# Basisboard_Weiche.net
KiCad netlist of a schematic drawn in EAGLE
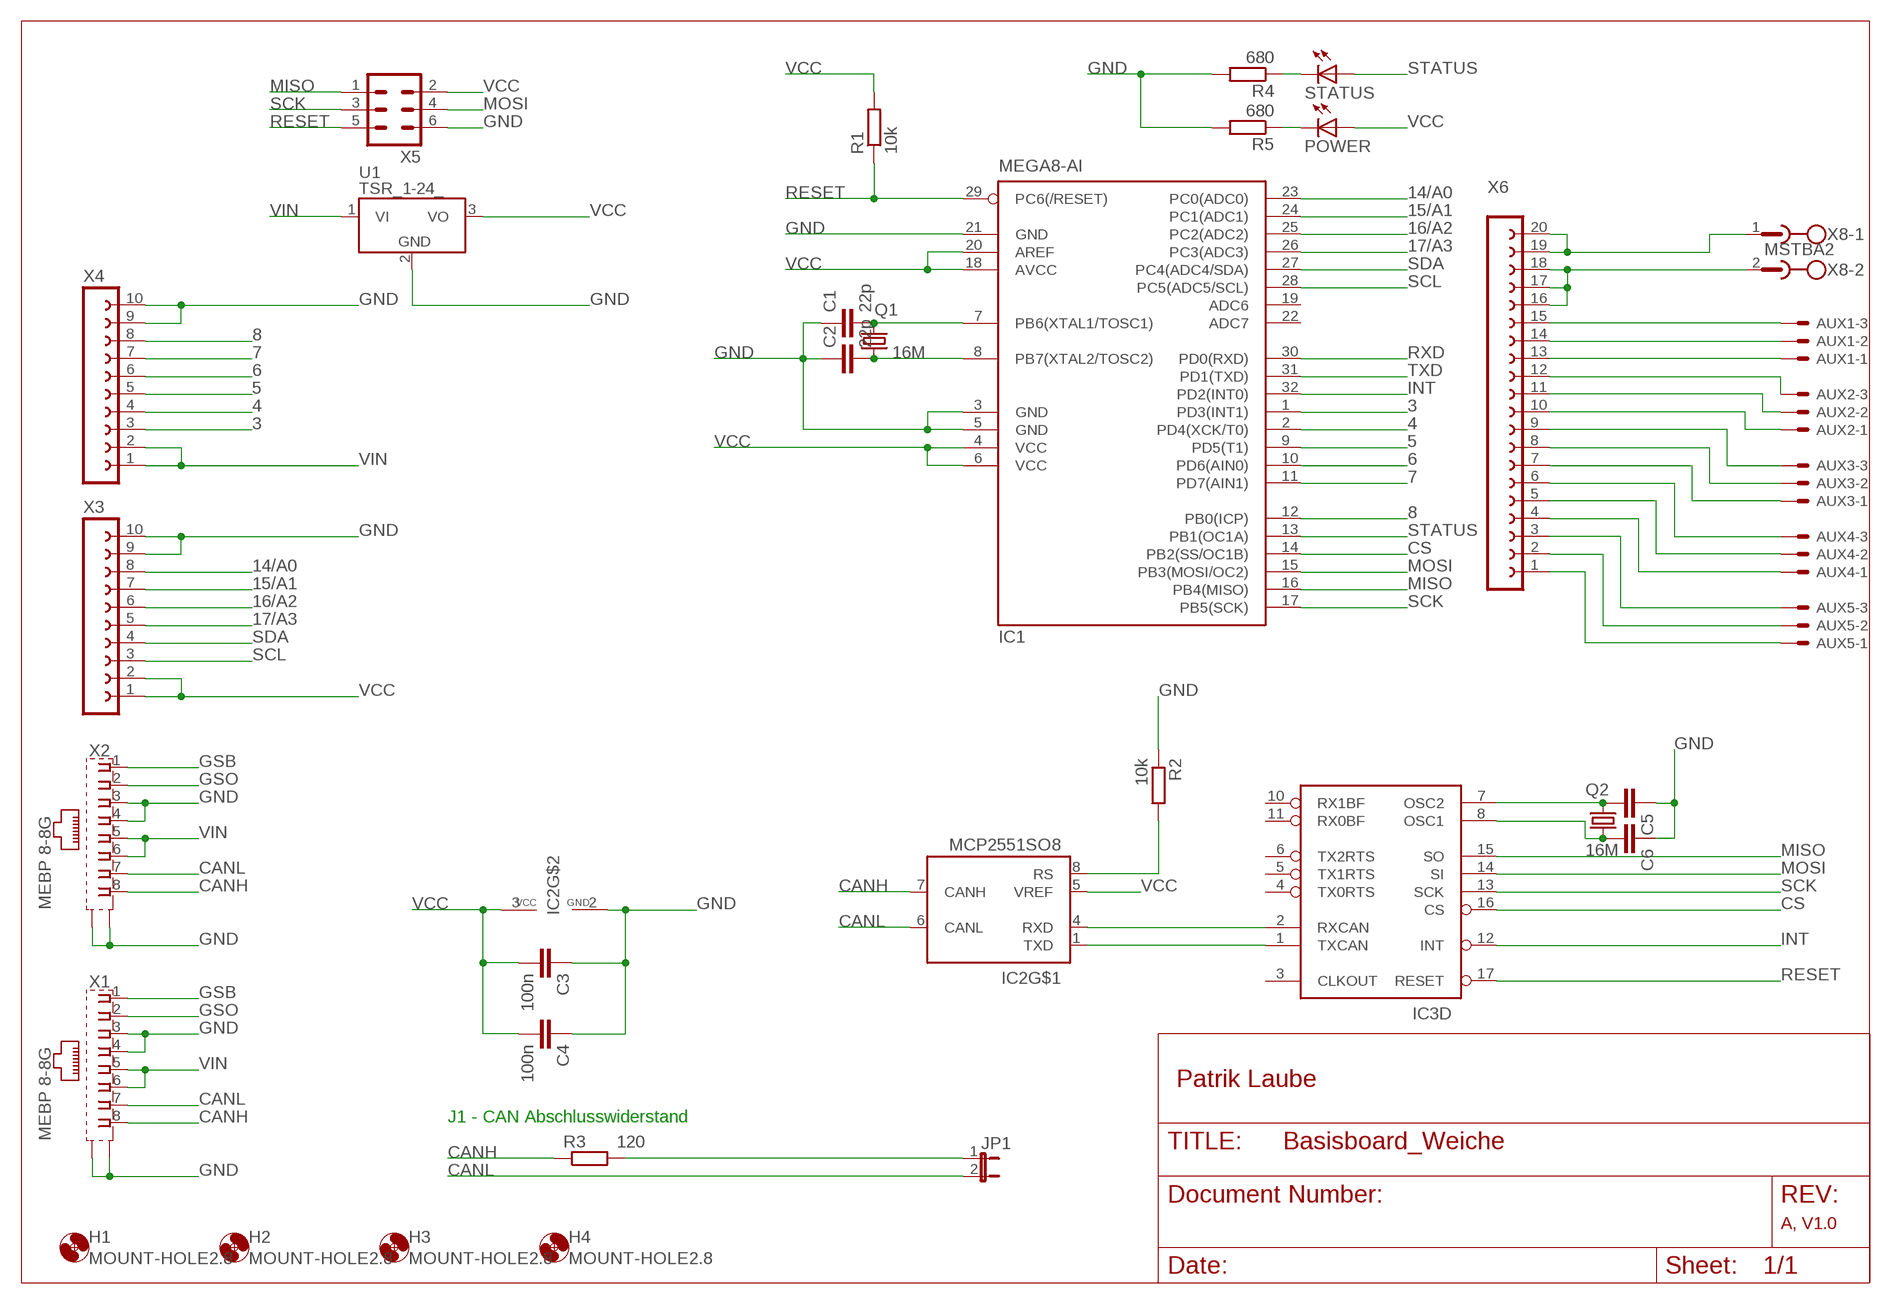
[diagram p0: schematic, sheet 1]

(export (version "E")
  (design (tool "Eeschema 10.0.6"))
  (components
    (comp (ref "AUX1")
      (value "22-27-2031-03")
      (footprint "eagle-import:6410-03")
      (fields (field (name "MF") "MOLEX"))
      (libsource (lib "eagle-import") (part "22-?-0327-2031"))
    )
    (comp (ref "AUX2")
      (value "22-27-2031-03")
      (footprint "eagle-import:6410-03")
      (fields (field (name "MF") "MOLEX"))
      (libsource (lib "eagle-import") (part "22-?-0327-2031"))
    )
    (comp (ref "AUX3")
      (value "22-27-2031-03")
      (footprint "eagle-import:6410-03")
      (fields (field (name "MF") "MOLEX"))
      (libsource (lib "eagle-import") (part "22-?-0327-2031"))
    )
    (comp (ref "AUX4")
      (value "22-27-2031-03")
      (footprint "eagle-import:6410-03")
      (fields (field (name "MF") "MOLEX"))
      (libsource (lib "eagle-import") (part "22-?-0327-2031"))
    )
    (comp (ref "AUX5")
      (value "22-27-2031-03")
      (footprint "eagle-import:6410-03")
      (fields (field (name "MF") "MOLEX"))
      (libsource (lib "eagle-import") (part "22-?-0327-2031"))
    )
    (comp (ref "C1")
      (value "22p")
      (footprint "eagle-import:C1206")
      (libsource (lib "eagle-import") (part "C-EUC1206"))
    )
    (comp (ref "C2")
      (value "22p")
      (footprint "eagle-import:C1206")
      (libsource (lib "eagle-import") (part "C-EUC1206"))
    )
    (comp (ref "C3")
      (value "100n")
      (footprint "eagle-import:C1206")
      (fields (field (name "LCSC_PART") "C24497"))
      (libsource (lib "eagle-import") (part "C-EUC1206"))
    )
    (comp (ref "C4")
      (value "100n")
      (footprint "eagle-import:C1206")
      (fields (field (name "LCSC_PART") "C24497"))
      (libsource (lib "eagle-import") (part "C-EUC1206"))
    )
    (comp (ref "C5")
      (value "C-EUC1206")
      (footprint "eagle-import:C1206")
      (libsource (lib "eagle-import") (part "C-EUC1206"))
    )
    (comp (ref "C6")
      (value "C-EUC1206")
      (footprint "eagle-import:C1206")
      (libsource (lib "eagle-import") (part "C-EUC1206"))
    )
    (comp (ref "H1")
      (value "MOUNT-HOLE2.8")
      (footprint "eagle-import:2,8")
      (libsource (lib "eagle-import") (part "MOUNT-HOLE2.8"))
    )
    (comp (ref "H2")
      (value "MOUNT-HOLE2.8")
      (footprint "eagle-import:2,8")
      (libsource (lib "eagle-import") (part "MOUNT-HOLE2.8"))
    )
    (comp (ref "H3")
      (value "MOUNT-HOLE2.8")
      (footprint "eagle-import:2,8")
      (libsource (lib "eagle-import") (part "MOUNT-HOLE2.8"))
    )
    (comp (ref "H4")
      (value "MOUNT-HOLE2.8")
      (footprint "eagle-import:2,8")
      (libsource (lib "eagle-import") (part "MOUNT-HOLE2.8"))
    )
    (comp (ref "IC1")
      (value "MEGA8-AI")
      (footprint "eagle-import:TQFP32-08")
      (fields (field (name "MPN") "ATMEGA8-16AU") (field (name "LCSC_PART") "C132230"))
      (libsource (lib "eagle-import") (part "MEGA8-AI"))
    )
    (comp (ref "IC2")
      (value "MCP2551SO8")
      (footprint "eagle-import:SO08")
      (fields (field (name "LCSC_PART") "C49558"))
      (libsource (lib "eagle-import") (part "MCP2551SO8"))
    )
    (comp (ref "IC3")
      (value "MCP2515SO")
      (footprint "eagle-import:SO-18W")
      (fields (field (name "LCSC_PART") " C153782"))
      (libsource (lib "eagle-import") (part "MCP2515SO"))
    )
    (comp (ref "JP1")
      (value "JP1E")
      (footprint "eagle-import:JP1")
      (libsource (lib "eagle-import") (part "JP1E"))
    )
    (comp (ref "POWER")
      (value "LEDCHIPLED_1206")
      (footprint "eagle-import:CHIPLED_1206")
      (fields (field (name "LCSC_PART") "C88326"))
      (libsource (lib "eagle-import") (part "LEDCHIPLED_1206"))
    )
    (comp (ref "Q1")
      (value "16M")
      (footprint "eagle-import:HC49_S")
      (libsource (lib "eagle-import") (part "CRYSTALHC49S"))
    )
    (comp (ref "Q2")
      (value "16M")
      (footprint "eagle-import:HC49_S")
      (libsource (lib "eagle-import") (part "CRYSTALHC49S"))
    )
    (comp (ref "R1")
      (value "10k")
      (footprint "eagle-import:R1206")
      (fields (field (name "LCSC_PART") " C17902"))
      (libsource (lib "eagle-import") (part "R-EU_R1206"))
    )
    (comp (ref "R2")
      (value "10k")
      (footprint "eagle-import:R1206")
      (fields (field (name "LCSC_PART") " C17902"))
      (libsource (lib "eagle-import") (part "R-EU_R1206"))
    )
    (comp (ref "R3")
      (value "120")
      (footprint "eagle-import:R1206")
      (libsource (lib "eagle-import") (part "rcl_334_R-EU_R1206"))
    )
    (comp (ref "R4")
      (value "680")
      (footprint "eagle-import:R1206")
      (libsource (lib "eagle-import") (part "R-EU_R1206"))
    )
    (comp (ref "R5")
      (value "680")
      (footprint "eagle-import:R1206")
      (libsource (lib "eagle-import") (part "R-EU_R1206"))
    )
    (comp (ref "STATUS")
      (value "LEDCHIPLED_1206")
      (footprint "eagle-import:CHIPLED_1206")
      (libsource (lib "eagle-import") (part "LEDCHIPLED_1206"))
    )
    (comp (ref "U1")
      (value "TSR_1-24_")
      (footprint "eagle-import:TSR-1")
      (libsource (lib "eagle-import") (part "TSR_1-24_"))
    )
    (comp (ref "X1")
      (value "MEBP 8-8G")
      (footprint "eagle-import:XRJF-01A-0-D2A-010")
      (libsource (lib "eagle-import") (part "XRJFMEBP-8-8G-01A-0-D22-020"))
    )
    (comp (ref "X2")
      (value "MEBP 8-8G")
      (footprint "eagle-import:XRJF-01A-0-D2A-010")
      (libsource (lib "eagle-import") (part "XRJFMEBP-8-8G-01A-0-D22-020"))
    )
    (comp (ref "X3")
      (value "FE10-1")
      (footprint "eagle-import:FE10")
      (libsource (lib "eagle-import") (part "FE10-1"))
    )
    (comp (ref "X4")
      (value "FE10-1")
      (footprint "eagle-import:FE10")
      (libsource (lib "eagle-import") (part "FE10-1"))
    )
    (comp (ref "X5")
      (value "ML6")
      (footprint "eagle-import:ML6")
      (libsource (lib "eagle-import") (part "ML6"))
    )
    (comp (ref "X6")
      (value "FE20-1")
      (footprint "eagle-import:FE20")
      (libsource (lib "eagle-import") (part "FE20-1"))
    )
    (comp (ref "X8")
      (value "MSTBA2")
      (footprint "eagle-import:MSTBA2")
      (fields (field (name "MF") "FARNELL") (field (name "MPN") "1757242"))
      (libsource (lib "eagle-import") (part "MSTBA2"))
    )
  )
  (nets
    (net (code "1") (name "/3") (class "Default")
      (node (ref "IC1") (pin "1") (pinfunction "PD3(INT1)_1") (pintype "bidirectional"))
      (node (ref "X4") (pin "3") (pinfunction "3_3") (pintype "passive"))
    )
    (net (code "2") (name "/4") (class "Default")
      (node (ref "IC1") (pin "2") (pinfunction "PD4(XCK/T0)_2") (pintype "bidirectional"))
      (node (ref "X4") (pin "4") (pinfunction "4_4") (pintype "passive"))
    )
    (net (code "3") (name "/5") (class "Default")
      (node (ref "IC1") (pin "9") (pinfunction "PD5(T1)_9") (pintype "bidirectional"))
      (node (ref "X4") (pin "5") (pinfunction "5_5") (pintype "passive"))
    )
    (net (code "4") (name "/6") (class "Default")
      (node (ref "IC1") (pin "10") (pinfunction "PD6(AIN0)_10") (pintype "bidirectional"))
      (node (ref "X4") (pin "6") (pinfunction "6_6") (pintype "passive"))
    )
    (net (code "5") (name "/7") (class "Default")
      (node (ref "IC1") (pin "11") (pinfunction "PD7(AIN1)_11") (pintype "bidirectional"))
      (node (ref "X4") (pin "7") (pinfunction "7_7") (pintype "passive"))
    )
    (net (code "6") (name "/8") (class "Default")
      (node (ref "IC1") (pin "12") (pinfunction "PB0(ICP)_12") (pintype "bidirectional"))
      (node (ref "X4") (pin "8") (pinfunction "8_8") (pintype "passive"))
    )
    (net (code "7") (name "/14{slash}A0") (class "Default")
      (node (ref "IC1") (pin "23") (pinfunction "PC0(ADC0)_23") (pintype "bidirectional"))
      (node (ref "X3") (pin "8") (pinfunction "8_8") (pintype "passive"))
    )
    (net (code "8") (name "/15{slash}A1") (class "Default")
      (node (ref "IC1") (pin "24") (pinfunction "PC1(ADC1)_24") (pintype "bidirectional"))
      (node (ref "X3") (pin "7") (pinfunction "7_7") (pintype "passive"))
    )
    (net (code "9") (name "/16{slash}A2") (class "Default")
      (node (ref "IC1") (pin "25") (pinfunction "PC2(ADC2)_25") (pintype "bidirectional"))
      (node (ref "X3") (pin "6") (pinfunction "6_6") (pintype "passive"))
    )
    (net (code "10") (name "/17{slash}A3") (class "Default")
      (node (ref "IC1") (pin "26") (pinfunction "PC3(ADC3)_26") (pintype "bidirectional"))
      (node (ref "X3") (pin "5") (pinfunction "5_5") (pintype "passive"))
    )
    (net (code "11") (name "/CANH") (class "Default")
      (node (ref "IC2") (pin "7") (pinfunction "CANH_7") (pintype "bidirectional"))
      (node (ref "R3") (pin "1") (pinfunction "1_1") (pintype "passive"))
      (node (ref "X1") (pin "8") (pinfunction "8_8") (pintype "passive"))
      (node (ref "X2") (pin "8") (pinfunction "8_8") (pintype "passive"))
    )
    (net (code "12") (name "/CANL") (class "Default")
      (node (ref "IC2") (pin "6") (pinfunction "CANL_6") (pintype "bidirectional"))
      (node (ref "JP1") (pin "2") (pinfunction "2_2") (pintype "passive"))
      (node (ref "X1") (pin "7") (pinfunction "7_7") (pintype "passive"))
      (node (ref "X2") (pin "7") (pinfunction "7_7") (pintype "passive"))
    )
    (net (code "13") (name "/CS") (class "Default")
      (node (ref "IC1") (pin "14") (pinfunction "PB2(SS/OC1B)_14") (pintype "bidirectional"))
      (node (ref "IC3") (pin "16") (pinfunction "CS_16") (pintype "input"))
    )
    (net (code "14") (name "/GND") (class "Default")
      (node (ref "C1") (pin "1") (pinfunction "1_1") (pintype "passive"))
      (node (ref "C2") (pin "1") (pinfunction "1_1") (pintype "passive"))
      (node (ref "C3") (pin "1") (pinfunction "1_1") (pintype "passive"))
      (node (ref "C4") (pin "1") (pinfunction "1_1") (pintype "passive"))
      (node (ref "C5") (pin "1") (pinfunction "1_1") (pintype "passive"))
      (node (ref "C6") (pin "1") (pinfunction "1_1") (pintype "passive"))
      (node (ref "IC1") (pin "21") (pinfunction "GND_21") (pintype "power_in"))
      (node (ref "IC1") (pin "3") (pinfunction "GND_3") (pintype "power_in"))
      (node (ref "IC1") (pin "5") (pinfunction "GND_5") (pintype "power_in"))
      (node (ref "IC2") (pin "2") (pinfunction "GND_2") (pintype "power_in"))
      (node (ref "R2") (pin "1") (pinfunction "1_1") (pintype "passive"))
      (node (ref "R4") (pin "2") (pinfunction "2_2") (pintype "passive"))
      (node (ref "R5") (pin "2") (pinfunction "2_2") (pintype "passive"))
      (node (ref "U1") (pin "2") (pinfunction "GND_2") (pintype "power_in"))
      (node (ref "X1") (pin "3") (pinfunction "3_3") (pintype "passive"))
      (node (ref "X1") (pin "4") (pinfunction "4_4") (pintype "passive"))
      (node (ref "X1") (pin "S1") (pinfunction "S_S1") (pintype "passive"))
      (node (ref "X1") (pin "S2") (pinfunction "S_S2") (pintype "passive"))
      (node (ref "X2") (pin "3") (pinfunction "3_3") (pintype "passive"))
      (node (ref "X2") (pin "4") (pinfunction "4_4") (pintype "passive"))
      (node (ref "X2") (pin "S1") (pinfunction "S_S1") (pintype "passive"))
      (node (ref "X2") (pin "S2") (pinfunction "S_S2") (pintype "passive"))
      (node (ref "X3") (pin "10") (pinfunction "10_10") (pintype "passive"))
      (node (ref "X3") (pin "9") (pinfunction "9_9") (pintype "passive"))
      (node (ref "X4") (pin "10") (pinfunction "10_10") (pintype "passive"))
      (node (ref "X4") (pin "9") (pinfunction "9_9") (pintype "passive"))
      (node (ref "X5") (pin "6") (pinfunction "6_6") (pintype "passive"))
    )
    (net (code "15") (name "/GSB") (class "Default")
      (node (ref "X1") (pin "1") (pinfunction "1_1") (pintype "passive"))
      (node (ref "X2") (pin "1") (pinfunction "1_1") (pintype "passive"))
    )
    (net (code "16") (name "/GSO") (class "Default")
      (node (ref "X1") (pin "2") (pinfunction "2_2") (pintype "passive"))
      (node (ref "X2") (pin "2") (pinfunction "2_2") (pintype "passive"))
    )
    (net (code "17") (name "/INT") (class "Default")
      (node (ref "IC1") (pin "32") (pinfunction "PD2(INT0)_32") (pintype "bidirectional"))
      (node (ref "IC3") (pin "12") (pinfunction "INT_12") (pintype "output"))
    )
    (net (code "18") (name "/MISO") (class "Default")
      (node (ref "IC1") (pin "16") (pinfunction "PB4(MISO)_16") (pintype "bidirectional"))
      (node (ref "IC3") (pin "15") (pinfunction "SO_15") (pintype "output"))
      (node (ref "X5") (pin "1") (pinfunction "1_1") (pintype "passive"))
    )
    (net (code "19") (name "/MOSI") (class "Default")
      (node (ref "IC1") (pin "15") (pinfunction "PB3(MOSI/OC2)_15") (pintype "bidirectional"))
      (node (ref "IC3") (pin "14") (pinfunction "SI_14") (pintype "input"))
      (node (ref "X5") (pin "4") (pinfunction "4_4") (pintype "passive"))
    )
    (net (code "20") (name "/RESET") (class "Default")
      (node (ref "IC1") (pin "29") (pinfunction "PC6(/RESET)_29") (pintype "bidirectional"))
      (node (ref "IC3") (pin "17") (pinfunction "RESET_17") (pintype "input"))
      (node (ref "R1") (pin "1") (pinfunction "1_1") (pintype "passive"))
      (node (ref "X5") (pin "5") (pinfunction "5_5") (pintype "passive"))
    )
    (net (code "21") (name "/RXD") (class "Default")
      (node (ref "IC1") (pin "30") (pinfunction "PD0(RXD)_30") (pintype "bidirectional"))
    )
    (net (code "22") (name "/SCK") (class "Default")
      (node (ref "IC1") (pin "17") (pinfunction "PB5(SCK)_17") (pintype "bidirectional"))
      (node (ref "IC3") (pin "13") (pinfunction "SCK_13") (pintype "input"))
      (node (ref "X5") (pin "3") (pinfunction "3_3") (pintype "passive"))
    )
    (net (code "23") (name "/SCL") (class "Default")
      (node (ref "IC1") (pin "28") (pinfunction "PC5(ADC5/SCL)_28") (pintype "bidirectional"))
      (node (ref "X3") (pin "3") (pinfunction "3_3") (pintype "passive"))
    )
    (net (code "24") (name "/SDA") (class "Default")
      (node (ref "IC1") (pin "27") (pinfunction "PC4(ADC4/SDA)_27") (pintype "bidirectional"))
      (node (ref "X3") (pin "4") (pinfunction "4_4") (pintype "passive"))
    )
    (net (code "25") (name "/STATUS") (class "Default")
      (node (ref "IC1") (pin "13") (pinfunction "PB1(OC1A)_13") (pintype "bidirectional"))
      (node (ref "STATUS") (pin "A") (pinfunction "A_A") (pintype "passive"))
    )
    (net (code "26") (name "/TXD") (class "Default")
      (node (ref "IC1") (pin "31") (pinfunction "PD1(TXD)_31") (pintype "bidirectional"))
    )
    (net (code "27") (name "/VCC") (class "Default")
      (node (ref "C3") (pin "2") (pinfunction "2_2") (pintype "passive"))
      (node (ref "C4") (pin "2") (pinfunction "2_2") (pintype "passive"))
      (node (ref "IC1") (pin "18") (pinfunction "AVCC_18") (pintype "power_in"))
      (node (ref "IC1") (pin "20") (pinfunction "AREF_20") (pintype "passive"))
      (node (ref "IC1") (pin "4") (pinfunction "VCC_4") (pintype "power_in"))
      (node (ref "IC1") (pin "6") (pinfunction "VCC_6") (pintype "power_in"))
      (node (ref "IC2") (pin "3") (pinfunction "VCC_3") (pintype "power_in"))
      (node (ref "IC2") (pin "5") (pinfunction "VREF_5") (pintype "bidirectional"))
      (node (ref "POWER") (pin "A") (pinfunction "A_A") (pintype "passive"))
      (node (ref "R1") (pin "2") (pinfunction "2_2") (pintype "passive"))
      (node (ref "U1") (pin "3") (pinfunction "VO_3") (pintype "power_in"))
      (node (ref "X3") (pin "1") (pinfunction "1_1") (pintype "passive"))
      (node (ref "X3") (pin "2") (pinfunction "2_2") (pintype "passive"))
      (node (ref "X5") (pin "2") (pinfunction "2_2") (pintype "passive"))
    )
    (net (code "28") (name "/VIN") (class "Default")
      (node (ref "U1") (pin "1") (pinfunction "VI_1") (pintype "power_in"))
      (node (ref "X1") (pin "5") (pinfunction "5_5") (pintype "passive"))
      (node (ref "X1") (pin "6") (pinfunction "6_6") (pintype "passive"))
      (node (ref "X2") (pin "5") (pinfunction "5_5") (pintype "passive"))
      (node (ref "X2") (pin "6") (pinfunction "6_6") (pintype "passive"))
      (node (ref "X4") (pin "1") (pinfunction "1_1") (pintype "passive"))
      (node (ref "X4") (pin "2") (pinfunction "2_2") (pintype "passive"))
    )
    (net (code "29") (name "Net-(AUX1A-S)") (class "Default")
      (node (ref "AUX1") (pin "1") (pinfunction "S_1") (pintype "passive"))
      (node (ref "X6") (pin "13") (pinfunction "13_13") (pintype "passive"))
    )
    (net (code "30") (name "Net-(AUX1B-S)") (class "Default")
      (node (ref "AUX1") (pin "2") (pinfunction "S_2") (pintype "passive"))
      (node (ref "X6") (pin "14") (pinfunction "14_14") (pintype "passive"))
    )
    (net (code "31") (name "Net-(AUX1C-S)") (class "Default")
      (node (ref "AUX1") (pin "3") (pinfunction "S_3") (pintype "passive"))
      (node (ref "X6") (pin "15") (pinfunction "15_15") (pintype "passive"))
    )
    (net (code "32") (name "Net-(AUX2A-S)") (class "Default")
      (node (ref "AUX2") (pin "1") (pinfunction "S_1") (pintype "passive"))
      (node (ref "X6") (pin "10") (pinfunction "10_10") (pintype "passive"))
    )
    (net (code "33") (name "Net-(AUX2B-S)") (class "Default")
      (node (ref "AUX2") (pin "2") (pinfunction "S_2") (pintype "passive"))
      (node (ref "X6") (pin "11") (pinfunction "11_11") (pintype "passive"))
    )
    (net (code "34") (name "Net-(AUX2C-S)") (class "Default")
      (node (ref "AUX2") (pin "3") (pinfunction "S_3") (pintype "passive"))
      (node (ref "X6") (pin "12") (pinfunction "12_12") (pintype "passive"))
    )
    (net (code "35") (name "Net-(AUX3A-S)") (class "Default")
      (node (ref "AUX3") (pin "1") (pinfunction "S_1") (pintype "passive"))
      (node (ref "X6") (pin "7") (pinfunction "7_7") (pintype "passive"))
    )
    (net (code "36") (name "Net-(AUX3B-S)") (class "Default")
      (node (ref "AUX3") (pin "2") (pinfunction "S_2") (pintype "passive"))
      (node (ref "X6") (pin "8") (pinfunction "8_8") (pintype "passive"))
    )
    (net (code "37") (name "Net-(AUX3C-S)") (class "Default")
      (node (ref "AUX3") (pin "3") (pinfunction "S_3") (pintype "passive"))
      (node (ref "X6") (pin "9") (pinfunction "9_9") (pintype "passive"))
    )
    (net (code "38") (name "Net-(AUX4A-S)") (class "Default")
      (node (ref "AUX4") (pin "1") (pinfunction "S_1") (pintype "passive"))
      (node (ref "X6") (pin "4") (pinfunction "4_4") (pintype "passive"))
    )
    (net (code "39") (name "Net-(AUX4B-S)") (class "Default")
      (node (ref "AUX4") (pin "2") (pinfunction "S_2") (pintype "passive"))
      (node (ref "X6") (pin "5") (pinfunction "5_5") (pintype "passive"))
    )
    (net (code "40") (name "Net-(AUX4C-S)") (class "Default")
      (node (ref "AUX4") (pin "3") (pinfunction "S_3") (pintype "passive"))
      (node (ref "X6") (pin "6") (pinfunction "6_6") (pintype "passive"))
    )
    (net (code "41") (name "Net-(AUX5A-S)") (class "Default")
      (node (ref "AUX5") (pin "1") (pinfunction "S_1") (pintype "passive"))
      (node (ref "X6") (pin "1") (pinfunction "1_1") (pintype "passive"))
    )
    (net (code "42") (name "Net-(AUX5B-S)") (class "Default")
      (node (ref "AUX5") (pin "2") (pinfunction "S_2") (pintype "passive"))
      (node (ref "X6") (pin "2") (pinfunction "2_2") (pintype "passive"))
    )
    (net (code "43") (name "Net-(AUX5C-S)") (class "Default")
      (node (ref "AUX5") (pin "3") (pinfunction "S_3") (pintype "passive"))
      (node (ref "X6") (pin "3") (pinfunction "3_3") (pintype "passive"))
    )
    (net (code "44") (name "Net-(IC1-PB6(XTAL1{slash}TOSC1))") (class "Default")
      (node (ref "C1") (pin "2") (pinfunction "2_2") (pintype "passive"))
      (node (ref "IC1") (pin "7") (pinfunction "PB6(XTAL1/TOSC1)_7") (pintype "bidirectional"))
      (node (ref "Q1") (pin "2") (pinfunction "2_2") (pintype "passive"))
    )
    (net (code "45") (name "Net-(IC1-PB7(XTAL2{slash}TOSC2))") (class "Default")
      (node (ref "C2") (pin "2") (pinfunction "2_2") (pintype "passive"))
      (node (ref "IC1") (pin "8") (pinfunction "PB7(XTAL2/TOSC2)_8") (pintype "bidirectional"))
      (node (ref "Q1") (pin "1") (pinfunction "1_1") (pintype "passive"))
    )
    (net (code "46") (name "Net-(IC2A-RS)") (class "Default")
      (node (ref "IC2") (pin "8") (pinfunction "RS_8") (pintype "bidirectional"))
      (node (ref "R2") (pin "2") (pinfunction "2_2") (pintype "passive"))
    )
    (net (code "47") (name "Net-(IC2A-RXD)") (class "Default")
      (node (ref "IC2") (pin "4") (pinfunction "RXD_4") (pintype "bidirectional"))
      (node (ref "IC3") (pin "2") (pinfunction "RXCAN_2") (pintype "input"))
    )
    (net (code "48") (name "Net-(IC2A-TXD)") (class "Default")
      (node (ref "IC2") (pin "1") (pinfunction "TXD_1") (pintype "bidirectional"))
      (node (ref "IC3") (pin "1") (pinfunction "TXCAN_1") (pintype "output"))
    )
    (net (code "49") (name "Net-(IC3A-OSC1)") (class "Default")
      (node (ref "C6") (pin "2") (pinfunction "2_2") (pintype "passive"))
      (node (ref "IC3") (pin "8") (pinfunction "OSC1_8") (pintype "input"))
      (node (ref "Q2") (pin "2") (pinfunction "2_2") (pintype "passive"))
    )
    (net (code "50") (name "Net-(IC3A-OSC2)") (class "Default")
      (node (ref "C5") (pin "2") (pinfunction "2_2") (pintype "passive"))
      (node (ref "IC3") (pin "7") (pinfunction "OSC2_7") (pintype "input"))
      (node (ref "Q2") (pin "1") (pinfunction "1_1") (pintype "passive"))
    )
    (net (code "51") (name "Net-(JP1-Pad1)") (class "Default")
      (node (ref "JP1") (pin "1") (pinfunction "1_1") (pintype "passive"))
      (node (ref "R3") (pin "2") (pinfunction "2_2") (pintype "passive"))
    )
    (net (code "52") (name "Net-(POWER-PadC)") (class "Default")
      (node (ref "POWER") (pin "C") (pinfunction "C_C") (pintype "passive"))
      (node (ref "R5") (pin "1") (pinfunction "1_1") (pintype "passive"))
    )
    (net (code "53") (name "Net-(R4-Pad1)") (class "Default")
      (node (ref "R4") (pin "1") (pinfunction "1_1") (pintype "passive"))
      (node (ref "STATUS") (pin "C") (pinfunction "C_C") (pintype "passive"))
    )
    (net (code "54") (name "Net-(X6-Pad19)") (class "Default")
      (node (ref "X6") (pin "19") (pinfunction "19_19") (pintype "passive"))
      (node (ref "X6") (pin "20") (pinfunction "20_20") (pintype "passive"))
      (node (ref "X8") (pin "1") (pinfunction "1_1") (pintype "passive"))
    )
    (net (code "55") (name "Net-(X8B-1)") (class "Default")
      (node (ref "X6") (pin "16") (pinfunction "16_16") (pintype "passive"))
      (node (ref "X6") (pin "17") (pinfunction "17_17") (pintype "passive"))
      (node (ref "X6") (pin "18") (pinfunction "18_18") (pintype "passive"))
      (node (ref "X8") (pin "2") (pinfunction "1_2") (pintype "passive"))
    )
    (net (code "56") (name "unconnected-(IC1-ADC6-Pad19)") (class "Default")
      (node (ref "IC1") (pin "19") (pinfunction "ADC6_19") (pintype "bidirectional"))
    )
    (net (code "57") (name "unconnected-(IC1-ADC7-Pad22)") (class "Default")
      (node (ref "IC1") (pin "22") (pinfunction "ADC7_22") (pintype "bidirectional"))
    )
    (net (code "58") (name "unconnected-(IC3A-CLKOUT-Pad3)") (class "Default")
      (node (ref "IC3") (pin "3") (pinfunction "CLKOUT_3") (pintype "output"))
    )
    (net (code "59") (name "unconnected-(IC3A-RX0BF-Pad11)") (class "Default")
      (node (ref "IC3") (pin "11") (pinfunction "RX0BF_11") (pintype "output"))
    )
    (net (code "60") (name "unconnected-(IC3A-RX1BF-Pad10)") (class "Default")
      (node (ref "IC3") (pin "10") (pinfunction "RX1BF_10") (pintype "output"))
    )
    (net (code "61") (name "unconnected-(IC3A-TX0RTS-Pad4)") (class "Default")
      (node (ref "IC3") (pin "4") (pinfunction "TX0RTS_4") (pintype "input"))
    )
    (net (code "62") (name "unconnected-(IC3A-TX1RTS-Pad5)") (class "Default")
      (node (ref "IC3") (pin "5") (pinfunction "TX1RTS_5") (pintype "input"))
    )
    (net (code "63") (name "unconnected-(IC3A-TX2RTS-Pad6)") (class "Default")
      (node (ref "IC3") (pin "6") (pinfunction "TX2RTS_6") (pintype "input"))
    )
  )
)
